# led-esp32.net
KiCad netlist of a schematic drawn in Altium Designer
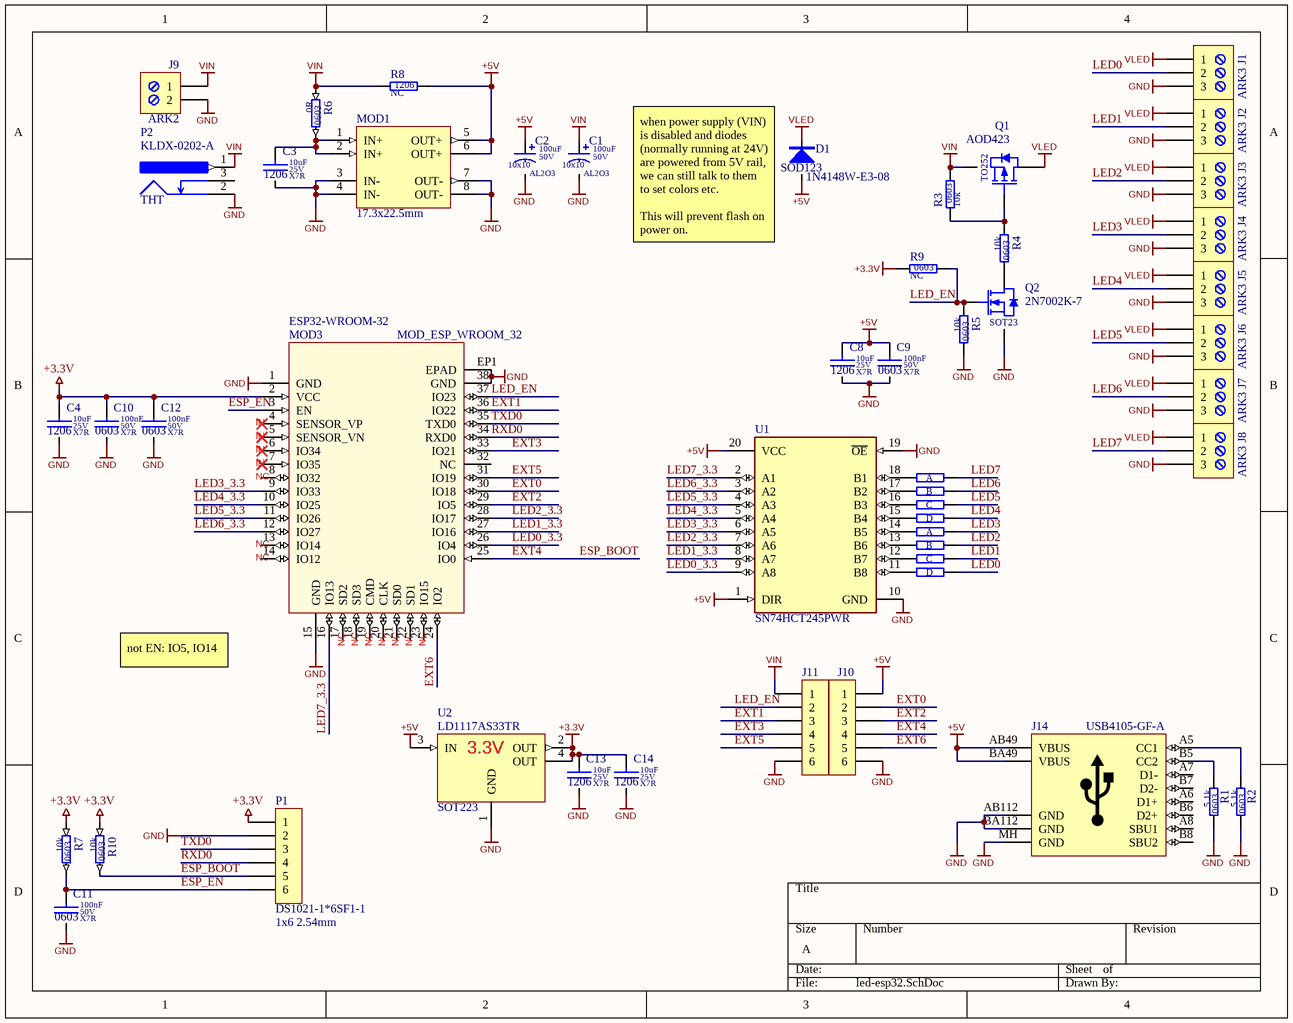
[diagram p0: led-esp32.SchDoc]

(export (version "E")
  (design (tool "Eeschema 10.0.6"))
  (components
    (comp (ref "C1")
      (value "100uF")
      (footprint "CE_D_10x10_SMD")
      (description "Polarized Capacitor")
      (fields
        (field (name "DIELECTRIC") "AL2O3")
        (field (name "SCH_FOOTPRINT") "10x10")
        (field (name "VOLTAGE") "50V")
        (field (name "PART NUMBER") "CE_100uF_50V_AL2O3_10x10_20")
        (field (name "MANUFACTURER") "Nichicon")
      )
      (libsource (lib "Library") (part "CE"))
    )
    (comp (ref "C2")
      (value "100uF")
      (footprint "CE_D_10x10_SMD")
      (description "Polarized Capacitor")
      (fields
        (field (name "DIELECTRIC") "AL2O3")
        (field (name "SCH_FOOTPRINT") "10x10")
        (field (name "VOLTAGE") "50V")
        (field (name "PART NUMBER") "CE_100uF_50V_AL2O3_10x10_20")
        (field (name "MANUFACTURER") "Nichicon")
      )
      (libsource (lib "Library") (part "CE"))
    )
    (comp (ref "C3")
      (value "10uF")
      (footprint "C_1206_3216")
      (description "Capacitor")
      (fields
        (field (name "DIELECTRIC") "X7R")
        (field (name "VOLTAGE") "25V")
        (field (name "SCH_FOOTPRINT") "1206")
        (field (name "PART NUMBER") "C_10uF_25V_X7R_1206_10")
        (field (name "MANUFACTURER") "Samsung")
      )
      (libsource (lib "Library") (part "C"))
    )
    (comp (ref "C4")
      (value "10uF")
      (footprint "C_1206_3216")
      (description "Capacitor")
      (fields
        (field (name "DIELECTRIC") "X7R")
        (field (name "VOLTAGE") "25V")
        (field (name "SCH_FOOTPRINT") "1206")
        (field (name "PART NUMBER") "C_10uF_25V_X7R_1206_10")
        (field (name "MANUFACTURER") "Samsung")
      )
      (libsource (lib "Library") (part "C"))
    )
    (comp (ref "C8")
      (value "10uF")
      (footprint "C_1206_3216")
      (description "Capacitor")
      (fields
        (field (name "DIELECTRIC") "X7R")
        (field (name "VOLTAGE") "25V")
        (field (name "SCH_FOOTPRINT") "1206")
        (field (name "PART NUMBER") "C_10uF_25V_X7R_1206_10")
        (field (name "MANUFACTURER") "Samsung")
      )
      (libsource (lib "Library") (part "C"))
    )
    (comp (ref "C9")
      (value "100nF")
      (footprint "C_0603_1608")
      (description "Capacitor")
      (fields
        (field (name "DIELECTRIC") "X7R")
        (field (name "VOLTAGE") "50V")
        (field (name "SCH_FOOTPRINT") "0603")
        (field (name "PART NUMBER") "C_100nF_50V_X7R_0603_5")
        (field (name "MANUFACTURER") "Samsung")
      )
      (libsource (lib "Library") (part "C"))
    )
    (comp (ref "C10")
      (value "100nF")
      (footprint "C_0603_1608")
      (description "Capacitor")
      (fields
        (field (name "DIELECTRIC") "X7R")
        (field (name "VOLTAGE") "50V")
        (field (name "SCH_FOOTPRINT") "0603")
        (field (name "PART NUMBER") "C_100nF_50V_X7R_0603_5")
        (field (name "MANUFACTURER") "Samsung")
      )
      (libsource (lib "Library") (part "C"))
    )
    (comp (ref "C11")
      (value "100nF")
      (footprint "C_0603_1608")
      (description "Capacitor")
      (fields
        (field (name "DIELECTRIC") "X7R")
        (field (name "VOLTAGE") "50V")
        (field (name "SCH_FOOTPRINT") "0603")
        (field (name "PART NUMBER") "C_100nF_50V_X7R_0603_5")
        (field (name "MANUFACTURER") "Samsung")
      )
      (libsource (lib "Library") (part "C"))
    )
    (comp (ref "C12")
      (value "100nF")
      (footprint "C_0603_1608")
      (description "Capacitor")
      (fields
        (field (name "DIELECTRIC") "X7R")
        (field (name "VOLTAGE") "50V")
        (field (name "SCH_FOOTPRINT") "0603")
        (field (name "PART NUMBER") "C_100nF_50V_X7R_0603_5")
        (field (name "MANUFACTURER") "Samsung")
      )
      (libsource (lib "Library") (part "C"))
    )
    (comp (ref "C13")
      (value "10uF")
      (footprint "C_1206_3216")
      (description "Capacitor")
      (fields
        (field (name "DIELECTRIC") "X7R")
        (field (name "VOLTAGE") "25V")
        (field (name "SCH_FOOTPRINT") "1206")
        (field (name "PART NUMBER") "C_10uF_25V_X7R_1206_10")
        (field (name "MANUFACTURER") "Samsung")
      )
      (libsource (lib "Library") (part "C"))
    )
    (comp (ref "C14")
      (value "10uF")
      (footprint "C_1206_3216")
      (description "Capacitor")
      (fields
        (field (name "DIELECTRIC") "X7R")
        (field (name "VOLTAGE") "25V")
        (field (name "SCH_FOOTPRINT") "1206")
        (field (name "PART NUMBER") "C_10uF_25V_X7R_1206_10")
        (field (name "MANUFACTURER") "Samsung")
      )
      (libsource (lib "Library") (part "C"))
    )
    (comp (ref "D1")
      (value "1N4148W-E3-08")
      (footprint "SOD123")
      (fields
        (field (name "SCH_FOOTPRINT") "SOD123")
        (field (name "PART NUMBER") "D_1N4148W_0A15_75V_SOD123")
        (field (name "VOLTAGE") "75")
        (field (name "MANUFACTURER") "Vishay")
      )
      (libsource (lib "Library") (part "D"))
    )
    (comp (ref "J1")
      (value "ARK3")
      (footprint "J_ARK3")
      (description "ARK Screw terminal, 3-Pin")
      (fields
        (field (name "SCH_FOOTPRINT") "ARK3")
        (field (name "PART NUMBER") "J_TB-5.0-P-3P")
        (field (name "MANUFACTURER") "DEGSON ELECTRONICS")
      )
      (libsource (lib "Library") (part "J_ARK3"))
    )
    (comp (ref "J2")
      (value "ARK3")
      (footprint "J_ARK3")
      (description "ARK Screw terminal, 3-Pin")
      (fields
        (field (name "SCH_FOOTPRINT") "ARK3")
        (field (name "PART NUMBER") "J_TB-5.0-P-3P")
        (field (name "MANUFACTURER") "DEGSON ELECTRONICS")
      )
      (libsource (lib "Library") (part "J_ARK3"))
    )
    (comp (ref "J3")
      (value "ARK3")
      (footprint "J_ARK3")
      (description "ARK Screw terminal, 3-Pin")
      (fields
        (field (name "SCH_FOOTPRINT") "ARK3")
        (field (name "PART NUMBER") "J_TB-5.0-P-3P")
        (field (name "MANUFACTURER") "DEGSON ELECTRONICS")
      )
      (libsource (lib "Library") (part "J_ARK3"))
    )
    (comp (ref "J4")
      (value "ARK3")
      (footprint "J_ARK3")
      (description "ARK Screw terminal, 3-Pin")
      (fields
        (field (name "SCH_FOOTPRINT") "ARK3")
        (field (name "PART NUMBER") "J_TB-5.0-P-3P")
        (field (name "MANUFACTURER") "DEGSON ELECTRONICS")
      )
      (libsource (lib "Library") (part "J_ARK3"))
    )
    (comp (ref "J5")
      (value "ARK3")
      (footprint "J_ARK3")
      (description "ARK Screw terminal, 3-Pin")
      (fields
        (field (name "SCH_FOOTPRINT") "ARK3")
        (field (name "PART NUMBER") "J_TB-5.0-P-3P")
        (field (name "MANUFACTURER") "DEGSON ELECTRONICS")
      )
      (libsource (lib "Library") (part "J_ARK3"))
    )
    (comp (ref "J6")
      (value "ARK3")
      (footprint "J_ARK3")
      (description "ARK Screw terminal, 3-Pin")
      (fields
        (field (name "SCH_FOOTPRINT") "ARK3")
        (field (name "PART NUMBER") "J_TB-5.0-P-3P")
        (field (name "MANUFACTURER") "DEGSON ELECTRONICS")
      )
      (libsource (lib "Library") (part "J_ARK3"))
    )
    (comp (ref "J7")
      (value "ARK3")
      (footprint "J_ARK3")
      (description "ARK Screw terminal, 3-Pin")
      (fields
        (field (name "SCH_FOOTPRINT") "ARK3")
        (field (name "PART NUMBER") "J_TB-5.0-P-3P")
        (field (name "MANUFACTURER") "DEGSON ELECTRONICS")
      )
      (libsource (lib "Library") (part "J_ARK3"))
    )
    (comp (ref "J8")
      (value "ARK3")
      (footprint "J_ARK3")
      (description "ARK Screw terminal, 3-Pin")
      (fields
        (field (name "SCH_FOOTPRINT") "ARK3")
        (field (name "PART NUMBER") "J_TB-5.0-P-3P")
        (field (name "MANUFACTURER") "DEGSON ELECTRONICS")
      )
      (libsource (lib "Library") (part "J_ARK3"))
    )
    (comp (ref "J9")
      (value "ARK2")
      (footprint "J_ARK2")
      (description "ARK Screw terminal, 2-Pin")
      (fields
        (field (name "SCH_FOOTPRINT") "ARK2")
        (field (name "PART NUMBER") "J_TB-5.0-P-2P")
        (field (name "MANUFACTURER") "DEGSON ELECTRONICS")
      )
      (libsource (lib "Library") (part "J_ARK2"))
    )
    (comp (ref "J10")
      (value "Goldpin female straight")
      (footprint "J_HEADER_1x6_2.54_VERTICAL")
      (description "Pin Header")
      (fields
        (field (name "PART NUMBER") "J_HEADER_1x6_2.54_VERTICAL")
        (field (name "MANUFACTURER") "Connfly")
      )
      (libsource (lib "Library") (part "J_HEADER_1x6"))
    )
    (comp (ref "J11")
      (value "Goldpin female straight")
      (footprint "J_HEADER_1x6_2.54_VERTICAL")
      (description "Pin Header")
      (fields
        (field (name "PART NUMBER") "J_HEADER_1x6_2.54_VERTICAL")
        (field (name "MANUFACTURER") "Connfly")
      )
      (libsource (lib "") (part "J_HEADER_1x6_1"))
    )
    (comp (ref "J14")
      (value "USB4105-GF-A")
      (footprint "J_USB_C_USB4105")
      (fields
        (field (name "PART NUMBER") "J_USB_C_USB4105-GF-A")
        (field (name "MANUFACTURER") "GCT")
        (field (name "Comment") "USB C Connector")
      )
      (libsource (lib "Library") (part "J_USB_C_2.0_USB4105"))
    )
    (comp (ref "MOD1")
      (value "Low cost, Aliexpress-ready DC-DC buck converter using MP1584")
      (footprint "MOD_BUCK_MP1584")
      (fields (field (name "SCH_FOOTPRINT") "17.3x22.5mm") (field (name "PART NUMBER") "MOD_BUCK_MP1584"))
      (libsource (lib "Library") (part "MOD_BUCK_MP1584"))
    )
    (comp (ref "MOD3")
      (value "ESP32-WROOM-32")
      (footprint "MOD_ESP_WROOM_32")
      (fields
        (field (name "SCH_FOOTPRINT") "MOD_ESP_WROOM_32")
        (field (name "PART NUMBER") "MOD_ESP32-WROOM-32")
        (field (name "MANUFACTURER") "ESPRESSIF")
        (field (name "Comment") "2.4 GHz Wi-Fi-and-Bluetooth combo chip")
      )
      (libsource (lib "Library") (part "MOD_ESP_WROOM_32"))
    )
    (comp (ref "P1")
      (value "DS1021-1*6SF1-1")
      (footprint "P_HEADER_1x6_2.54")
      (description "Pin Header")
      (fields
        (field (name "PART NUMBER") "P_HEADER_1x6_2.54")
        (field (name "SCH_FOOTPRINT") "1x6 2.54mm")
        (field (name "MANUFACTURER") "Connfly")
      )
      (libsource (lib "Library") (part "P_HEADER_1x6"))
    )
    (comp (ref "P2")
      (value "KLDX-0202-A")
      (footprint "P_KLDX-0202-A")
      (description "Typical 3-pin jack power connector with switch")
      (fields
        (field (name "SCH_FOOTPRINT") "THT")
        (field (name "PART NUMBER") "P_KLDX-0202-A")
        (field (name "MANUFACTURER") "Kycon")
      )
      (libsource (lib "Library") (part "P_DC_JACK"))
    )
    (comp (ref "Q1")
      (value "AOD423")
      (footprint "DPAK_TO252-3_SC63_M")
      (fields
        (field (name "SCH_FOOTPRINT") "TO252")
        (field (name "PART NUMBER") "QP_AOD423")
        (field (name "VOLTAGE") "30V")
        (field (name "MANUFACTURER") "Alpha&Omega Semiconductor")
      )
      (libsource (lib "Library") (part "QP_GDS"))
    )
    (comp (ref "Q2")
      (value "2N7002K-7")
      (footprint "SOT23_TO236_SC59")
      (fields
        (field (name "SCH_FOOTPRINT") "SOT23")
        (field (name "PART NUMBER") "QN_2N7002K-7")
        (field (name "VOLTAGE") "60V")
        (field (name "MANUFACTURER") "Diodes Inc")
      )
      (libsource (lib "Library") (part "QN_GSD"))
    )
    (comp (ref "R1")
      (value "5.1k")
      (footprint "R_0603_1608")
      (fields
        (field (name "SCH_FOOTPRINT") "0603")
        (field (name "PART NUMBER") "R_5.1k_0603_1")
        (field (name "VOLTAGE") "75V")
        (field (name "POWER") "100mW")
      )
      (libsource (lib "Library") (part "R"))
    )
    (comp (ref "R2")
      (value "5.1k")
      (footprint "R_0603_1608")
      (fields
        (field (name "SCH_FOOTPRINT") "0603")
        (field (name "PART NUMBER") "R_5.1k_0603_1")
        (field (name "VOLTAGE") "75V")
        (field (name "POWER") "100mW")
      )
      (libsource (lib "Library") (part "R"))
    )
    (comp (ref "R3")
      (value "10k")
      (footprint "R_0603_1608")
      (fields
        (field (name "SCH_FOOTPRINT") "0603")
        (field (name "PART NUMBER") "R_10k_0603_1")
        (field (name "VOLTAGE") "75V")
        (field (name "POWER") "100mW")
      )
      (libsource (lib "Library") (part "R"))
    )
    (comp (ref "R4")
      (value "10k")
      (footprint "R_0603_1608")
      (fields
        (field (name "SCH_FOOTPRINT") "0603")
        (field (name "PART NUMBER") "R_10k_0603_1")
        (field (name "VOLTAGE") "75V")
        (field (name "POWER") "100mW")
      )
      (libsource (lib "Library") (part "R"))
    )
    (comp (ref "R5")
      (value "10k")
      (footprint "R_0603_1608")
      (fields
        (field (name "SCH_FOOTPRINT") "0603")
        (field (name "PART NUMBER") "R_10k_0603_1")
        (field (name "VOLTAGE") "75V")
        (field (name "POWER") "100mW")
      )
      (libsource (lib "Library") (part "R"))
    )
    (comp (ref "R6")
      (value "0R")
      (footprint "R_0603_1608")
      (fields
        (field (name "SCH_FOOTPRINT") "0603")
        (field (name "PART NUMBER") "R_0R_0603_1")
        (field (name "VOLTAGE") "75V")
        (field (name "POWER") "100mW")
      )
      (libsource (lib "") (part "R_1"))
    )
    (comp (ref "R7")
      (value "10k")
      (footprint "R_0603_1608")
      (fields
        (field (name "SCH_FOOTPRINT") "0603")
        (field (name "PART NUMBER") "R_10k_0603_1_AECQ0")
        (field (name "VOLTAGE") "75V")
        (field (name "POWER") "100mW")
      )
      (libsource (lib "") (part "R_1"))
    )
    (comp (ref "R8")
      (value "NC")
      (footprint "R_NC_1206_3216")
      (fields
        (field (name "SCH_FOOTPRINT") "1206")
        (field (name "PART NUMBER") "R_GENERIC_1206")
        (field (name "Comment") "Resistor")
      )
      (libsource (lib "Library") (part "R"))
    )
    (comp (ref "R9")
      (value "NC")
      (footprint "R_NC_0603_1608")
      (fields
        (field (name "SCH_FOOTPRINT") "0603")
        (field (name "PART NUMBER") "R_GENERIC_0603")
        (field (name "Comment") "Resistor")
      )
      (libsource (lib "Library") (part "R"))
    )
    (comp (ref "R10")
      (value "10k")
      (footprint "R_0603_1608")
      (fields
        (field (name "SCH_FOOTPRINT") "0603")
        (field (name "PART NUMBER") "R_10k_0603_1_AECQ0")
        (field (name "VOLTAGE") "75V")
        (field (name "POWER") "100mW")
      )
      (libsource (lib "") (part "R_1"))
    )
    (comp (ref "RN1")
      (value "Resistors Network")
      (footprint "RN4_0804_2010")
      (fields
        (field (name "PART NUMBER") "RN4_120R_0804_5")
        (field (name "VOLTAGE") "50V")
        (field (name "POWER") "63mW")
      )
      (libsource (lib "Library") (part "RN4"))
    )
    (comp (ref "RN2")
      (value "Resistors Network")
      (footprint "RN4_0804_2010")
      (fields
        (field (name "PART NUMBER") "RN4_120R_0804_5")
        (field (name "VOLTAGE") "50V")
        (field (name "POWER") "63mW")
      )
      (libsource (lib "Library") (part "RN4"))
    )
    (comp (ref "U1")
      (value "SN74HCT245PWR")
      (footprint "FP-PW0020A-MFG")
      (description "IC TXRX NON-INVERT 5.5V 20TSSOP")
      (libsource (lib "Altium Content Vault") (part "76fe970679da0e390ff693ee897d809"))
    )
    (comp (ref "U2")
      (value "LD1117AS33TR")
      (footprint "SOT223_SC73")
      (description "typical configuration")
      (fields
        (field (name "SCH_FOOTPRINT") "SOT223")
        (field (name "PART NUMBER") "VL_LD1117AS33TR_3V3_1A2")
        (field (name "VOLTAGE") "3.3V")
      )
      (libsource (lib "Library") (part "VL_4pin_3_1_2,4"))
    )
  )
  (nets
    (net (code "1") (name "+3.3V") (class "Default")
      (node (ref "C10") (pin "1") (pinfunction "1_1") (pintype "passive"))
      (node (ref "C12") (pin "1") (pinfunction "1_1") (pintype "passive"))
      (node (ref "C13") (pin "1") (pinfunction "1_1") (pintype "passive"))
      (node (ref "C14") (pin "1") (pinfunction "1_1") (pintype "passive"))
      (node (ref "C4") (pin "1") (pinfunction "1_1") (pintype "passive"))
      (node (ref "MOD3") (pin "2") (pinfunction "VCC_2") (pintype "input"))
      (node (ref "P1") (pin "1") (pinfunction "1_1") (pintype "passive"))
      (node (ref "R10") (pin "1") (pinfunction "1_1") (pintype "input"))
      (node (ref "R7") (pin "1") (pinfunction "1_1") (pintype "input"))
      (node (ref "R9") (pin "1") (pinfunction "1_1") (pintype "passive"))
      (node (ref "U2") (pin "2") (pinfunction "OUT_2") (pintype "output"))
      (node (ref "U2") (pin "4") (pinfunction "OUT_4") (pintype "passive"))
    )
    (net (code "2") (name "+5V") (class "Default")
      (node (ref "C2") (pin "1") (pinfunction "1_1") (pintype "passive"))
      (node (ref "C8") (pin "1") (pinfunction "1_1") (pintype "passive"))
      (node (ref "C9") (pin "1") (pinfunction "1_1") (pintype "passive"))
      (node (ref "D1") (pin "2") (pintype "passive"))
      (node (ref "J10") (pin "1") (pinfunction "1_1") (pintype "passive"))
      (node (ref "J14") (pin "AB49") (pinfunction "VBUS_AB49") (pintype "power_in"))
      (node (ref "J14") (pin "BA49") (pinfunction "VBUS_BA49") (pintype "power_in"))
      (node (ref "MOD1") (pin "5") (pinfunction "OUT+_5") (pintype "output"))
      (node (ref "MOD1") (pin "6") (pinfunction "OUT+_6") (pintype "passive"))
      (node (ref "R8") (pin "2") (pinfunction "2_2") (pintype "passive"))
      (node (ref "U1") (pin "1") (pinfunction "DIR_1") (pintype "input"))
      (node (ref "U1") (pin "20") (pinfunction "VCC_20") (pintype "power_in"))
      (node (ref "U2") (pin "3") (pinfunction "IN_3") (pintype "input"))
    )
    (net (code "3") (name "/ESP_BOOT") (class "Default")
      (node (ref "J10") (pin "4") (pinfunction "4_4") (pintype "passive"))
      (node (ref "MOD3") (pin "25") (pinfunction "IO0_25") (pintype "input"))
      (node (ref "P1") (pin "5") (pinfunction "5_5") (pintype "passive"))
      (node (ref "R10") (pin "2") (pinfunction "2_2") (pintype "output"))
    )
    (net (code "4") (name "/ESP_EN") (class "Default")
      (node (ref "C11") (pin "1") (pinfunction "1_1") (pintype "passive"))
      (node (ref "MOD3") (pin "3") (pinfunction "EN_3") (pintype "input"))
      (node (ref "P1") (pin "6") (pinfunction "6_6") (pintype "passive"))
      (node (ref "R7") (pin "2") (pinfunction "2_2") (pintype "output"))
    )
    (net (code "5") (name "/EXT0") (class "Default")
      (node (ref "J10") (pin "2") (pinfunction "2_2") (pintype "passive"))
      (node (ref "MOD3") (pin "30") (pinfunction "IO18_30") (pintype "bidirectional"))
    )
    (net (code "6") (name "/EXT1") (class "Default")
      (node (ref "J11") (pin "3") (pinfunction "3_3") (pintype "passive"))
      (node (ref "MOD3") (pin "36") (pinfunction "IO22_36") (pintype "bidirectional"))
    )
    (net (code "7") (name "/EXT2") (class "Default")
      (node (ref "J10") (pin "3") (pinfunction "3_3") (pintype "passive"))
      (node (ref "MOD3") (pin "29") (pinfunction "IO5_29") (pintype "bidirectional"))
    )
    (net (code "8") (name "/EXT3") (class "Default")
      (node (ref "J11") (pin "4") (pinfunction "4_4") (pintype "passive"))
      (node (ref "MOD3") (pin "33") (pinfunction "IO21_33") (pintype "bidirectional"))
    )
    (net (code "9") (name "/EXT5") (class "Default")
      (node (ref "J11") (pin "5") (pinfunction "5_5") (pintype "passive"))
      (node (ref "MOD3") (pin "31") (pinfunction "IO19_31") (pintype "bidirectional"))
    )
    (net (code "10") (name "/EXT6") (class "Default")
      (node (ref "J10") (pin "5") (pinfunction "5_5") (pintype "passive"))
      (node (ref "MOD3") (pin "24") (pinfunction "IO2_24") (pintype "bidirectional"))
    )
    (net (code "11") (name "/LED0") (class "Default")
      (node (ref "J1") (pin "2") (pinfunction "2_2") (pintype "passive"))
      (node (ref "RN2") (pin "5") (pinfunction "5_5") (pintype "passive"))
    )
    (net (code "12") (name "/LED0_3.3") (class "Default")
      (node (ref "MOD3") (pin "26") (pinfunction "IO4_26") (pintype "bidirectional"))
      (node (ref "U1") (pin "9") (pinfunction "A8_9") (pintype "bidirectional"))
    )
    (net (code "13") (name "/LED1") (class "Default")
      (node (ref "J2") (pin "2") (pinfunction "2_2") (pintype "passive"))
      (node (ref "RN2") (pin "6") (pinfunction "6_6") (pintype "passive"))
    )
    (net (code "14") (name "/LED1_3.3") (class "Default")
      (node (ref "MOD3") (pin "27") (pinfunction "IO16_27") (pintype "bidirectional"))
      (node (ref "U1") (pin "8") (pinfunction "A7_8") (pintype "bidirectional"))
    )
    (net (code "15") (name "/LED2") (class "Default")
      (node (ref "J3") (pin "2") (pinfunction "2_2") (pintype "passive"))
      (node (ref "RN2") (pin "7") (pinfunction "7_7") (pintype "passive"))
    )
    (net (code "16") (name "/LED2_3.3") (class "Default")
      (node (ref "MOD3") (pin "28") (pinfunction "IO17_28") (pintype "bidirectional"))
      (node (ref "U1") (pin "7") (pinfunction "A6_7") (pintype "bidirectional"))
    )
    (net (code "17") (name "/LED3") (class "Default")
      (node (ref "J4") (pin "2") (pinfunction "2_2") (pintype "passive"))
      (node (ref "RN2") (pin "8") (pinfunction "8_8") (pintype "passive"))
    )
    (net (code "18") (name "/LED3_3.3") (class "Default")
      (node (ref "MOD3") (pin "9") (pinfunction "IO33_9") (pintype "bidirectional"))
      (node (ref "U1") (pin "6") (pinfunction "A5_6") (pintype "bidirectional"))
    )
    (net (code "19") (name "/LED4") (class "Default")
      (node (ref "J5") (pin "2") (pinfunction "2_2") (pintype "passive"))
      (node (ref "RN1") (pin "5") (pinfunction "5_5") (pintype "passive"))
    )
    (net (code "20") (name "/LED4_3.3") (class "Default")
      (node (ref "MOD3") (pin "10") (pinfunction "IO25_10") (pintype "bidirectional"))
      (node (ref "U1") (pin "5") (pinfunction "A4_5") (pintype "bidirectional"))
    )
    (net (code "21") (name "/LED5") (class "Default")
      (node (ref "J6") (pin "2") (pinfunction "2_2") (pintype "passive"))
      (node (ref "RN1") (pin "6") (pinfunction "6_6") (pintype "passive"))
    )
    (net (code "22") (name "/LED5_3.3") (class "Default")
      (node (ref "MOD3") (pin "11") (pinfunction "IO26_11") (pintype "bidirectional"))
      (node (ref "U1") (pin "4") (pinfunction "A3_4") (pintype "bidirectional"))
    )
    (net (code "23") (name "/LED6") (class "Default")
      (node (ref "J7") (pin "2") (pinfunction "2_2") (pintype "passive"))
      (node (ref "RN1") (pin "7") (pinfunction "7_7") (pintype "passive"))
    )
    (net (code "24") (name "/LED6_3.3") (class "Default")
      (node (ref "MOD3") (pin "12") (pinfunction "IO27_12") (pintype "bidirectional"))
      (node (ref "U1") (pin "3") (pinfunction "A2_3") (pintype "bidirectional"))
    )
    (net (code "25") (name "/LED7") (class "Default")
      (node (ref "J8") (pin "2") (pinfunction "2_2") (pintype "passive"))
      (node (ref "RN1") (pin "8") (pinfunction "8_8") (pintype "passive"))
    )
    (net (code "26") (name "/LED7_3.3") (class "Default")
      (node (ref "MOD3") (pin "16") (pinfunction "IO13_16") (pintype "bidirectional"))
      (node (ref "U1") (pin "2") (pinfunction "A1_2") (pintype "bidirectional"))
    )
    (net (code "27") (name "/LED_EN") (class "Default")
      (node (ref "J11") (pin "2") (pinfunction "2_2") (pintype "passive"))
      (node (ref "MOD3") (pin "37") (pinfunction "IO23_37") (pintype "bidirectional"))
      (node (ref "Q2") (pin "1") (pinfunction "G_1") (pintype "passive"))
      (node (ref "R5") (pin "1") (pinfunction "1_1") (pintype "passive"))
      (node (ref "R9") (pin "2") (pinfunction "2_2") (pintype "passive"))
    )
    (net (code "28") (name "/RXD0") (class "Default")
      (node (ref "MOD3") (pin "34") (pinfunction "RXD0_34") (pintype "bidirectional"))
      (node (ref "P1") (pin "4") (pinfunction "4_4") (pintype "passive"))
    )
    (net (code "29") (name "/TXD0") (class "Default")
      (node (ref "MOD3") (pin "35") (pinfunction "TXD0_35") (pintype "bidirectional"))
      (node (ref "P1") (pin "3") (pinfunction "3_3") (pintype "passive"))
    )
    (net (code "30") (name "GND") (class "Default")
      (node (ref "C1") (pin "2") (pinfunction "2_2") (pintype "passive"))
      (node (ref "C10") (pin "2") (pinfunction "2_2") (pintype "passive"))
      (node (ref "C11") (pin "2") (pinfunction "2_2") (pintype "passive"))
      (node (ref "C12") (pin "2") (pinfunction "2_2") (pintype "passive"))
      (node (ref "C13") (pin "2") (pinfunction "2_2") (pintype "passive"))
      (node (ref "C14") (pin "2") (pinfunction "2_2") (pintype "passive"))
      (node (ref "C2") (pin "2") (pinfunction "2_2") (pintype "passive"))
      (node (ref "C3") (pin "2") (pinfunction "2_2") (pintype "passive"))
      (node (ref "C4") (pin "2") (pinfunction "2_2") (pintype "passive"))
      (node (ref "C8") (pin "2") (pinfunction "2_2") (pintype "passive"))
      (node (ref "C9") (pin "2") (pinfunction "2_2") (pintype "passive"))
      (node (ref "J1") (pin "3") (pinfunction "3_3") (pintype "passive"))
      (node (ref "J10") (pin "6") (pinfunction "6_6") (pintype "passive"))
      (node (ref "J11") (pin "6") (pinfunction "6_6") (pintype "passive"))
      (node (ref "J14") (pin "AB112") (pinfunction "GND_AB112") (pintype "power_in"))
      (node (ref "J14") (pin "BA112") (pinfunction "GND_BA112") (pintype "power_in"))
      (node (ref "J14") (pin "MH") (pinfunction "GND_MH") (pintype "power_in"))
      (node (ref "J2") (pin "3") (pinfunction "3_3") (pintype "passive"))
      (node (ref "J3") (pin "3") (pinfunction "3_3") (pintype "passive"))
      (node (ref "J4") (pin "3") (pinfunction "3_3") (pintype "passive"))
      (node (ref "J5") (pin "3") (pinfunction "3_3") (pintype "passive"))
      (node (ref "J6") (pin "3") (pinfunction "3_3") (pintype "passive"))
      (node (ref "J7") (pin "3") (pinfunction "3_3") (pintype "passive"))
      (node (ref "J8") (pin "3") (pinfunction "3_3") (pintype "passive"))
      (node (ref "J9") (pin "2") (pinfunction "2_2") (pintype "passive"))
      (node (ref "MOD1") (pin "3") (pinfunction "IN-_3") (pintype "power_in"))
      (node (ref "MOD1") (pin "4") (pinfunction "IN-_4") (pintype "power_in"))
      (node (ref "MOD1") (pin "7") (pinfunction "OUT-_7") (pintype "output"))
      (node (ref "MOD1") (pin "8") (pinfunction "OUT-_8") (pintype "passive"))
      (node (ref "MOD3") (pin "1") (pinfunction "GND_1") (pintype "power_in"))
      (node (ref "MOD3") (pin "15") (pinfunction "GND_15") (pintype "power_in"))
      (node (ref "MOD3") (pin "38") (pinfunction "GND_38") (pintype "power_in"))
      (node (ref "MOD3") (pin "EP1") (pinfunction "EPAD_EP1") (pintype "power_in"))
      (node (ref "P1") (pin "2") (pinfunction "2_2") (pintype "passive"))
      (node (ref "P2") (pin "2") (pinfunction "2_2") (pintype "passive"))
      (node (ref "Q2") (pin "2") (pinfunction "S_2") (pintype "passive"))
      (node (ref "R1") (pin "2") (pinfunction "2_2") (pintype "passive"))
      (node (ref "R2") (pin "2") (pinfunction "2_2") (pintype "passive"))
      (node (ref "R5") (pin "2") (pinfunction "2_2") (pintype "passive"))
      (node (ref "U1") (pin "10") (pinfunction "GND_10") (pintype "power_in"))
      (node (ref "U1") (pin "19") (pinfunction "~{OE}_19") (pintype "input"))
      (node (ref "U2") (pin "1") (pinfunction "GND_1") (pintype "power_in"))
    )
    (net (code "31") (name "Net-(C3-Pad1)") (class "Default")
      (node (ref "C3") (pin "1") (pinfunction "1_1") (pintype "passive"))
      (node (ref "MOD1") (pin "1") (pinfunction "IN+_1") (pintype "input"))
      (node (ref "MOD1") (pin "2") (pinfunction "IN+_2") (pintype "input"))
      (node (ref "R6") (pin "2") (pinfunction "2_2") (pintype "output"))
    )
    (net (code "32") (name "Net-(J14-CC1)") (class "Default")
      (node (ref "J14") (pin "A5") (pinfunction "CC1_A5") (pintype "bidirectional"))
      (node (ref "R2") (pin "1") (pinfunction "1_1") (pintype "passive"))
    )
    (net (code "33") (name "Net-(J14-CC2)") (class "Default")
      (node (ref "J14") (pin "B5") (pinfunction "CC2_B5") (pintype "bidirectional"))
      (node (ref "R1") (pin "1") (pinfunction "1_1") (pintype "passive"))
    )
    (net (code "34") (name "Net-(Q1-G)") (class "Default")
      (node (ref "Q1") (pin "1") (pinfunction "G_1") (pintype "passive"))
      (node (ref "R3") (pin "1") (pinfunction "1_1") (pintype "passive"))
      (node (ref "R4") (pin "1") (pinfunction "1_1") (pintype "passive"))
    )
    (net (code "35") (name "Net-(Q2-D)") (class "Default")
      (node (ref "Q2") (pin "3") (pinfunction "D_3") (pintype "passive"))
      (node (ref "R4") (pin "2") (pinfunction "2_2") (pintype "passive"))
    )
    (net (code "36") (name "Net-(U1-B1)") (class "Default")
      (node (ref "RN1") (pin "1") (pinfunction "1_1") (pintype "passive"))
      (node (ref "U1") (pin "18") (pinfunction "B1_18") (pintype "bidirectional"))
    )
    (net (code "37") (name "Net-(U1-B2)") (class "Default")
      (node (ref "RN1") (pin "2") (pinfunction "2_2") (pintype "passive"))
      (node (ref "U1") (pin "17") (pinfunction "B2_17") (pintype "bidirectional"))
    )
    (net (code "38") (name "Net-(U1-B3)") (class "Default")
      (node (ref "RN1") (pin "3") (pinfunction "3_3") (pintype "passive"))
      (node (ref "U1") (pin "16") (pinfunction "B3_16") (pintype "bidirectional"))
    )
    (net (code "39") (name "Net-(U1-B4)") (class "Default")
      (node (ref "RN1") (pin "4") (pinfunction "4_4") (pintype "passive"))
      (node (ref "U1") (pin "15") (pinfunction "B4_15") (pintype "bidirectional"))
    )
    (net (code "40") (name "Net-(U1-B5)") (class "Default")
      (node (ref "RN2") (pin "1") (pinfunction "1_1") (pintype "passive"))
      (node (ref "U1") (pin "14") (pinfunction "B5_14") (pintype "bidirectional"))
    )
    (net (code "41") (name "Net-(U1-B6)") (class "Default")
      (node (ref "RN2") (pin "2") (pinfunction "2_2") (pintype "passive"))
      (node (ref "U1") (pin "13") (pinfunction "B6_13") (pintype "bidirectional"))
    )
    (net (code "42") (name "Net-(U1-B7)") (class "Default")
      (node (ref "RN2") (pin "3") (pinfunction "3_3") (pintype "passive"))
      (node (ref "U1") (pin "12") (pinfunction "B7_12") (pintype "bidirectional"))
    )
    (net (code "43") (name "Net-(U1-B8)") (class "Default")
      (node (ref "RN2") (pin "4") (pinfunction "4_4") (pintype "passive"))
      (node (ref "U1") (pin "11") (pinfunction "B8_11") (pintype "bidirectional"))
    )
    (net (code "44") (name "VIN") (class "Default")
      (node (ref "C1") (pin "1") (pinfunction "1_1") (pintype "passive"))
      (node (ref "J11") (pin "1") (pinfunction "1_1") (pintype "passive"))
      (node (ref "J9") (pin "1") (pinfunction "1_1") (pintype "passive"))
      (node (ref "P2") (pin "1") (pinfunction "1_1") (pintype "output"))
      (node (ref "Q1") (pin "3") (pinfunction "S_3") (pintype "passive"))
      (node (ref "R3") (pin "2") (pinfunction "2_2") (pintype "passive"))
      (node (ref "R6") (pin "1") (pinfunction "1_1") (pintype "input"))
      (node (ref "R8") (pin "1") (pinfunction "1_1") (pintype "passive"))
    )
    (net (code "45") (name "VLED") (class "Default")
      (node (ref "D1") (pin "1") (pintype "passive"))
      (node (ref "J1") (pin "1") (pinfunction "1_1") (pintype "passive"))
      (node (ref "J2") (pin "1") (pinfunction "1_1") (pintype "passive"))
      (node (ref "J3") (pin "1") (pinfunction "1_1") (pintype "passive"))
      (node (ref "J4") (pin "1") (pinfunction "1_1") (pintype "passive"))
      (node (ref "J5") (pin "1") (pinfunction "1_1") (pintype "passive"))
      (node (ref "J6") (pin "1") (pinfunction "1_1") (pintype "passive"))
      (node (ref "J7") (pin "1") (pinfunction "1_1") (pintype "passive"))
      (node (ref "J8") (pin "1") (pinfunction "1_1") (pintype "passive"))
      (node (ref "Q1") (pin "2") (pinfunction "D_2") (pintype "passive"))
    )
    (net (code "46") (name "unconnected-(J14-D1+-PadA6)") (class "Default")
      (node (ref "J14") (pin "A6") (pinfunction "D1+_A6") (pintype "bidirectional"))
    )
    (net (code "47") (name "unconnected-(J14-D1--PadA7)") (class "Default")
      (node (ref "J14") (pin "A7") (pinfunction "D1-_A7") (pintype "bidirectional"))
    )
    (net (code "48") (name "unconnected-(J14-D2+-PadB6)") (class "Default")
      (node (ref "J14") (pin "B6") (pinfunction "D2+_B6") (pintype "bidirectional"))
    )
    (net (code "49") (name "unconnected-(J14-D2--PadB7)") (class "Default")
      (node (ref "J14") (pin "B7") (pinfunction "D2-_B7") (pintype "bidirectional"))
    )
    (net (code "50") (name "unconnected-(J14-SBU1-PadA8)") (class "Default")
      (node (ref "J14") (pin "A8") (pinfunction "SBU1_A8") (pintype "bidirectional"))
    )
    (net (code "51") (name "unconnected-(J14-SBU2-PadB8)") (class "Default")
      (node (ref "J14") (pin "B8") (pinfunction "SBU2_B8") (pintype "bidirectional"))
    )
    (net (code "52") (name "unconnected-(MOD3-CLK-Pad20)") (class "Default")
      (node (ref "MOD3") (pin "20") (pinfunction "CLK_20") (pintype "bidirectional"))
    )
    (net (code "53") (name "unconnected-(MOD3-CMD-Pad19)") (class "Default")
      (node (ref "MOD3") (pin "19") (pinfunction "CMD_19") (pintype "bidirectional"))
    )
    (net (code "54") (name "unconnected-(MOD3-IO12-Pad14)") (class "Default")
      (node (ref "MOD3") (pin "14") (pinfunction "IO12_14") (pintype "bidirectional"))
    )
    (net (code "55") (name "unconnected-(MOD3-IO14-Pad13)") (class "Default")
      (node (ref "MOD3") (pin "13") (pinfunction "IO14_13") (pintype "bidirectional"))
    )
    (net (code "56") (name "unconnected-(MOD3-IO15-Pad23)") (class "Default")
      (node (ref "MOD3") (pin "23") (pinfunction "IO15_23") (pintype "bidirectional"))
    )
    (net (code "57") (name "unconnected-(MOD3-IO32-Pad8)") (class "Default")
      (node (ref "MOD3") (pin "8") (pinfunction "IO32_8") (pintype "bidirectional"))
    )
    (net (code "58") (name "unconnected-(MOD3-IO34-Pad6)") (class "Default")
      (node (ref "MOD3") (pin "6") (pinfunction "IO34_6") (pintype "input+no_connect"))
    )
    (net (code "59") (name "unconnected-(MOD3-IO35-Pad7)") (class "Default")
      (node (ref "MOD3") (pin "7") (pinfunction "IO35_7") (pintype "input+no_connect"))
    )
    (net (code "60") (name "unconnected-(MOD3-NC-Pad32)") (class "Default")
      (node (ref "MOD3") (pin "32") (pinfunction "NC_32") (pintype "passive"))
    )
    (net (code "61") (name "unconnected-(MOD3-SD0-Pad21)") (class "Default")
      (node (ref "MOD3") (pin "21") (pinfunction "SD0_21") (pintype "bidirectional"))
    )
    (net (code "62") (name "unconnected-(MOD3-SD1-Pad22)") (class "Default")
      (node (ref "MOD3") (pin "22") (pinfunction "SD1_22") (pintype "bidirectional"))
    )
    (net (code "63") (name "unconnected-(MOD3-SD2-Pad17)") (class "Default")
      (node (ref "MOD3") (pin "17") (pinfunction "SD2_17") (pintype "bidirectional"))
    )
    (net (code "64") (name "unconnected-(MOD3-SD3-Pad18)") (class "Default")
      (node (ref "MOD3") (pin "18") (pinfunction "SD3_18") (pintype "bidirectional"))
    )
    (net (code "65") (name "unconnected-(MOD3-SENSOR_VN-Pad5)") (class "Default")
      (node (ref "MOD3") (pin "5") (pinfunction "SENSOR_VN_5") (pintype "input+no_connect"))
    )
    (net (code "66") (name "unconnected-(MOD3-SENSOR_VP-Pad4)") (class "Default")
      (node (ref "MOD3") (pin "4") (pinfunction "SENSOR_VP_4") (pintype "input+no_connect"))
    )
    (net (code "67") (name "unconnected-(P2-Pad3)") (class "Default")
      (node (ref "P2") (pin "3") (pinfunction "3_3") (pintype "passive"))
    )
  )
)
